# CANcape.net
KiCad netlist of a schematic drawn in EAGLE
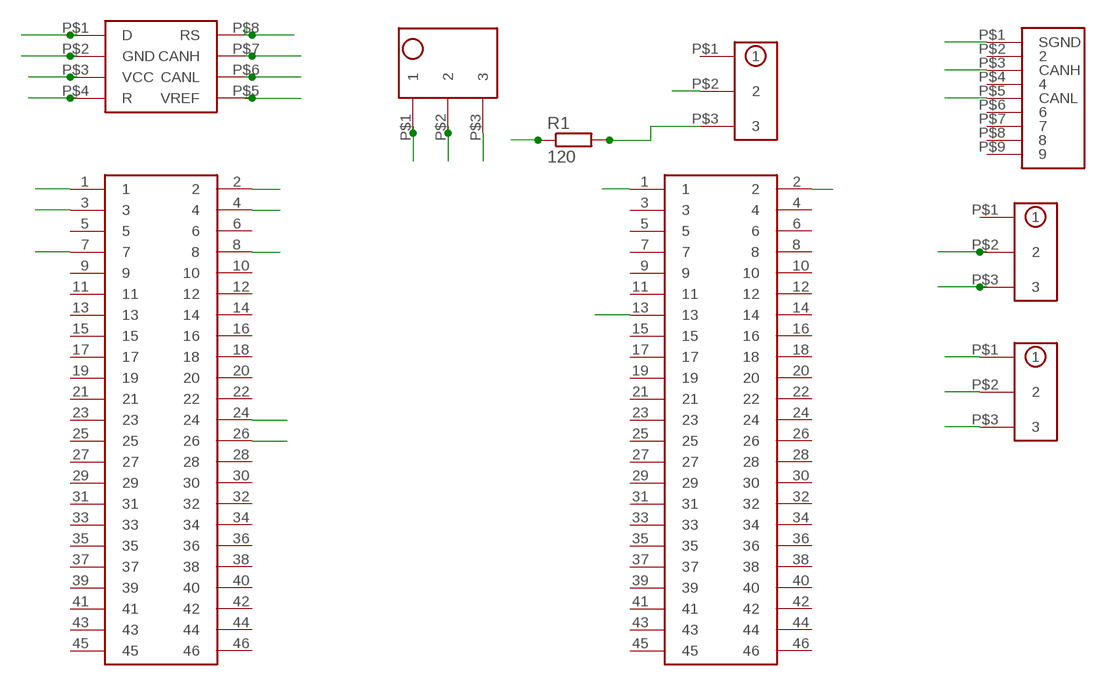
[diagram p0: schematic, sheet 1]

(export (version "E")
  (design (tool "Eeschema 10.0.6"))
  (components
    (comp (ref "R1")
      (value "120")
      (footprint "eagle-import:0207_15")
      (libsource (lib "eagle-import") (part "R-EU_0207/15"))
    )
    (comp (ref "U$1")
      (value "2X23_STACKABLE_HEADERS")
      (footprint "eagle-import:2X23_STACKABLE-HEADERS")
      (libsource (lib "eagle-import") (part "2X23_STACKABLE_HEADERS"))
    )
    (comp (ref "U$2")
      (value "2X23_STACKABLE_HEADERS")
      (footprint "eagle-import:2X23_STACKABLE-HEADERS")
      (libsource (lib "eagle-import") (part "2X23_STACKABLE_HEADERS"))
    )
    (comp (ref "U$3")
      (value "TB-5.0-PT-3P")
      (footprint "eagle-import:TB-5.0-PT-3P")
      (libsource (lib "eagle-import") (part "TB-5.0-PT-3P"))
    )
    (comp (ref "U$4")
      (value "1X3_HEADER")
      (footprint "eagle-import:1X3_HEADER")
      (libsource (lib "eagle-import") (part "1X3_HEADER"))
    )
    (comp (ref "U$5")
      (value "SOIC_BREAKOUT")
      (footprint "eagle-import:SOIC_BREAKOUT")
      (libsource (lib "eagle-import") (part "SOIC_BREAKOUT"))
    )
    (comp (ref "U$6")
      (value "DB9_BREAKOUT")
      (footprint "eagle-import:DB9_BREAKOUT")
      (libsource (lib "eagle-import") (part "DB9_BREAKOUT"))
    )
    (comp (ref "U$7")
      (value "1X3_HEADER")
      (footprint "eagle-import:1X3_HEADER")
      (libsource (lib "eagle-import") (part "1X3_HEADER"))
    )
    (comp (ref "U$8")
      (value "1X3_HEADER")
      (footprint "eagle-import:1X3_HEADER")
      (libsource (lib "eagle-import") (part "1X3_HEADER"))
    )
  )
  (nets
    (net (code "1") (name "/3.3V") (class "Default")
      (node (ref "U$1") (pin "3") (pinfunction "3_3") (pintype "bidirectional"))
      (node (ref "U$1") (pin "4") (pinfunction "4_4") (pintype "bidirectional"))
      (node (ref "U$5") (pin "P$5") (pinfunction "VREF_P$5") (pintype "bidirectional"))
      (node (ref "U$8") (pin "P$1") (pinfunction "1_P$1") (pintype "bidirectional"))
    )
    (net (code "2") (name "/5V") (class "Default")
      (node (ref "U$1") (pin "7") (pinfunction "7_7") (pintype "bidirectional"))
      (node (ref "U$1") (pin "8") (pinfunction "8_8") (pintype "bidirectional"))
      (node (ref "U$8") (pin "P$3") (pinfunction "3_P$3") (pintype "bidirectional"))
    )
    (net (code "3") (name "/CANH") (class "Default")
      (node (ref "U$3") (pin "P$1") (pinfunction "1_P$1") (pintype "bidirectional"))
      (node (ref "U$4") (pin "P$2") (pinfunction "2_P$2") (pintype "bidirectional"))
      (node (ref "U$5") (pin "P$7") (pinfunction "CANH_P$7") (pintype "bidirectional"))
      (node (ref "U$6") (pin "P$3") (pinfunction "CANH_P$3") (pintype "bidirectional"))
    )
    (net (code "4") (name "/CANL") (class "Default")
      (node (ref "R1") (pin "1") (pinfunction "1_1") (pintype "passive"))
      (node (ref "U$3") (pin "P$2") (pinfunction "2_P$2") (pintype "bidirectional"))
      (node (ref "U$5") (pin "P$6") (pinfunction "CANL_P$6") (pintype "bidirectional"))
      (node (ref "U$6") (pin "P$5") (pinfunction "CANL_P$5") (pintype "bidirectional"))
    )
    (net (code "5") (name "/DCAN1_RX") (class "Default")
      (node (ref "U$1") (pin "24") (pinfunction "24_24") (pintype "bidirectional"))
      (node (ref "U$5") (pin "P$4") (pinfunction "R_P$4") (pintype "bidirectional"))
    )
    (net (code "6") (name "/DCAN1_TX") (class "Default")
      (node (ref "U$1") (pin "26") (pinfunction "26_26") (pintype "bidirectional"))
      (node (ref "U$5") (pin "P$1") (pinfunction "D_P$1") (pintype "bidirectional"))
    )
    (net (code "7") (name "/GND") (class "Default")
      (node (ref "U$1") (pin "1") (pinfunction "1_1") (pintype "bidirectional"))
      (node (ref "U$1") (pin "2") (pinfunction "2_2") (pintype "bidirectional"))
      (node (ref "U$2") (pin "1") (pinfunction "1_1") (pintype "bidirectional"))
      (node (ref "U$2") (pin "2") (pinfunction "2_2") (pintype "bidirectional"))
      (node (ref "U$5") (pin "P$2") (pinfunction "GND_P$2") (pintype "bidirectional"))
      (node (ref "U$7") (pin "P$3") (pinfunction "3_P$3") (pintype "bidirectional"))
    )
    (net (code "8") (name "/SGND") (class "Default")
      (node (ref "U$3") (pin "P$3") (pinfunction "3_P$3") (pintype "bidirectional"))
      (node (ref "U$6") (pin "P$1") (pinfunction "SGND_P$1") (pintype "bidirectional"))
      (node (ref "U$7") (pin "P$2") (pinfunction "2_P$2") (pintype "bidirectional"))
    )
    (net (code "9") (name "/STANDBY") (class "Default")
      (node (ref "U$2") (pin "13") (pinfunction "13_13") (pintype "bidirectional"))
      (node (ref "U$5") (pin "P$8") (pinfunction "RS_P$8") (pintype "bidirectional"))
    )
    (net (code "10") (name "/TRAN_PWR") (class "Default")
      (node (ref "U$5") (pin "P$3") (pinfunction "VCC_P$3") (pintype "bidirectional"))
      (node (ref "U$8") (pin "P$2") (pinfunction "2_P$2") (pintype "bidirectional"))
    )
    (net (code "11") (name "Net-(U$4-3)") (class "Default")
      (node (ref "R1") (pin "2") (pinfunction "2_2") (pintype "passive"))
      (node (ref "U$4") (pin "P$3") (pinfunction "3_P$3") (pintype "bidirectional"))
    )
    (net (code "12") (name "unconnected-(U$1-Pad5)") (class "Default")
      (node (ref "U$1") (pin "5") (pinfunction "5_5") (pintype "bidirectional"))
    )
    (net (code "13") (name "unconnected-(U$1-Pad6)") (class "Default")
      (node (ref "U$1") (pin "6") (pinfunction "6_6") (pintype "bidirectional"))
    )
    (net (code "14") (name "unconnected-(U$1-Pad9)") (class "Default")
      (node (ref "U$1") (pin "9") (pinfunction "9_9") (pintype "bidirectional"))
    )
    (net (code "15") (name "unconnected-(U$1-Pad10)") (class "Default")
      (node (ref "U$1") (pin "10") (pinfunction "10_10") (pintype "bidirectional"))
    )
    (net (code "16") (name "unconnected-(U$1-Pad11)") (class "Default")
      (node (ref "U$1") (pin "11") (pinfunction "11_11") (pintype "bidirectional"))
    )
    (net (code "17") (name "unconnected-(U$1-Pad12)") (class "Default")
      (node (ref "U$1") (pin "12") (pinfunction "12_12") (pintype "bidirectional"))
    )
    (net (code "18") (name "unconnected-(U$1-Pad13)") (class "Default")
      (node (ref "U$1") (pin "13") (pinfunction "13_13") (pintype "bidirectional"))
    )
    (net (code "19") (name "unconnected-(U$1-Pad14)") (class "Default")
      (node (ref "U$1") (pin "14") (pinfunction "14_14") (pintype "bidirectional"))
    )
    (net (code "20") (name "unconnected-(U$1-Pad15)") (class "Default")
      (node (ref "U$1") (pin "15") (pinfunction "15_15") (pintype "bidirectional"))
    )
    (net (code "21") (name "unconnected-(U$1-Pad16)") (class "Default")
      (node (ref "U$1") (pin "16") (pinfunction "16_16") (pintype "bidirectional"))
    )
    (net (code "22") (name "unconnected-(U$1-Pad17)") (class "Default")
      (node (ref "U$1") (pin "17") (pinfunction "17_17") (pintype "bidirectional"))
    )
    (net (code "23") (name "unconnected-(U$1-Pad18)") (class "Default")
      (node (ref "U$1") (pin "18") (pinfunction "18_18") (pintype "bidirectional"))
    )
    (net (code "24") (name "unconnected-(U$1-Pad19)") (class "Default")
      (node (ref "U$1") (pin "19") (pinfunction "19_19") (pintype "bidirectional"))
    )
    (net (code "25") (name "unconnected-(U$1-Pad20)") (class "Default")
      (node (ref "U$1") (pin "20") (pinfunction "20_20") (pintype "bidirectional"))
    )
    (net (code "26") (name "unconnected-(U$1-Pad21)") (class "Default")
      (node (ref "U$1") (pin "21") (pinfunction "21_21") (pintype "bidirectional"))
    )
    (net (code "27") (name "unconnected-(U$1-Pad22)") (class "Default")
      (node (ref "U$1") (pin "22") (pinfunction "22_22") (pintype "bidirectional"))
    )
    (net (code "28") (name "unconnected-(U$1-Pad23)") (class "Default")
      (node (ref "U$1") (pin "23") (pinfunction "23_23") (pintype "bidirectional"))
    )
    (net (code "29") (name "unconnected-(U$1-Pad25)") (class "Default")
      (node (ref "U$1") (pin "25") (pinfunction "25_25") (pintype "bidirectional"))
    )
    (net (code "30") (name "unconnected-(U$1-Pad27)") (class "Default")
      (node (ref "U$1") (pin "27") (pinfunction "27_27") (pintype "bidirectional"))
    )
    (net (code "31") (name "unconnected-(U$1-Pad28)") (class "Default")
      (node (ref "U$1") (pin "28") (pinfunction "28_28") (pintype "bidirectional"))
    )
    (net (code "32") (name "unconnected-(U$1-Pad29)") (class "Default")
      (node (ref "U$1") (pin "29") (pinfunction "29_29") (pintype "bidirectional"))
    )
    (net (code "33") (name "unconnected-(U$1-Pad30)") (class "Default")
      (node (ref "U$1") (pin "30") (pinfunction "30_30") (pintype "bidirectional"))
    )
    (net (code "34") (name "unconnected-(U$1-Pad31)") (class "Default")
      (node (ref "U$1") (pin "31") (pinfunction "31_31") (pintype "bidirectional"))
    )
    (net (code "35") (name "unconnected-(U$1-Pad32)") (class "Default")
      (node (ref "U$1") (pin "32") (pinfunction "32_32") (pintype "bidirectional"))
    )
    (net (code "36") (name "unconnected-(U$1-Pad33)") (class "Default")
      (node (ref "U$1") (pin "33") (pinfunction "33_33") (pintype "bidirectional"))
    )
    (net (code "37") (name "unconnected-(U$1-Pad34)") (class "Default")
      (node (ref "U$1") (pin "34") (pinfunction "34_34") (pintype "bidirectional"))
    )
    (net (code "38") (name "unconnected-(U$1-Pad35)") (class "Default")
      (node (ref "U$1") (pin "35") (pinfunction "35_35") (pintype "bidirectional"))
    )
    (net (code "39") (name "unconnected-(U$1-Pad36)") (class "Default")
      (node (ref "U$1") (pin "36") (pinfunction "36_36") (pintype "bidirectional"))
    )
    (net (code "40") (name "unconnected-(U$1-Pad37)") (class "Default")
      (node (ref "U$1") (pin "37") (pinfunction "37_37") (pintype "bidirectional"))
    )
    (net (code "41") (name "unconnected-(U$1-Pad38)") (class "Default")
      (node (ref "U$1") (pin "38") (pinfunction "38_38") (pintype "bidirectional"))
    )
    (net (code "42") (name "unconnected-(U$1-Pad39)") (class "Default")
      (node (ref "U$1") (pin "39") (pinfunction "39_39") (pintype "bidirectional"))
    )
    (net (code "43") (name "unconnected-(U$1-Pad40)") (class "Default")
      (node (ref "U$1") (pin "40") (pinfunction "40_40") (pintype "bidirectional"))
    )
    (net (code "44") (name "unconnected-(U$1-Pad41)") (class "Default")
      (node (ref "U$1") (pin "41") (pinfunction "41_41") (pintype "bidirectional"))
    )
    (net (code "45") (name "unconnected-(U$1-Pad42)") (class "Default")
      (node (ref "U$1") (pin "42") (pinfunction "42_42") (pintype "bidirectional"))
    )
    (net (code "46") (name "unconnected-(U$1-Pad43)") (class "Default")
      (node (ref "U$1") (pin "43") (pinfunction "43_43") (pintype "bidirectional"))
    )
    (net (code "47") (name "unconnected-(U$1-Pad44)") (class "Default")
      (node (ref "U$1") (pin "44") (pinfunction "44_44") (pintype "bidirectional"))
    )
    (net (code "48") (name "unconnected-(U$1-Pad45)") (class "Default")
      (node (ref "U$1") (pin "45") (pinfunction "45_45") (pintype "bidirectional"))
    )
    (net (code "49") (name "unconnected-(U$1-Pad46)") (class "Default")
      (node (ref "U$1") (pin "46") (pinfunction "46_46") (pintype "bidirectional"))
    )
    (net (code "50") (name "unconnected-(U$2-Pad3)") (class "Default")
      (node (ref "U$2") (pin "3") (pinfunction "3_3") (pintype "bidirectional"))
    )
    (net (code "51") (name "unconnected-(U$2-Pad4)") (class "Default")
      (node (ref "U$2") (pin "4") (pinfunction "4_4") (pintype "bidirectional"))
    )
    (net (code "52") (name "unconnected-(U$2-Pad5)") (class "Default")
      (node (ref "U$2") (pin "5") (pinfunction "5_5") (pintype "bidirectional"))
    )
    (net (code "53") (name "unconnected-(U$2-Pad6)") (class "Default")
      (node (ref "U$2") (pin "6") (pinfunction "6_6") (pintype "bidirectional"))
    )
    (net (code "54") (name "unconnected-(U$2-Pad7)") (class "Default")
      (node (ref "U$2") (pin "7") (pinfunction "7_7") (pintype "bidirectional"))
    )
    (net (code "55") (name "unconnected-(U$2-Pad8)") (class "Default")
      (node (ref "U$2") (pin "8") (pinfunction "8_8") (pintype "bidirectional"))
    )
    (net (code "56") (name "unconnected-(U$2-Pad9)") (class "Default")
      (node (ref "U$2") (pin "9") (pinfunction "9_9") (pintype "bidirectional"))
    )
    (net (code "57") (name "unconnected-(U$2-Pad10)") (class "Default")
      (node (ref "U$2") (pin "10") (pinfunction "10_10") (pintype "bidirectional"))
    )
    (net (code "58") (name "unconnected-(U$2-Pad11)") (class "Default")
      (node (ref "U$2") (pin "11") (pinfunction "11_11") (pintype "bidirectional"))
    )
    (net (code "59") (name "unconnected-(U$2-Pad12)") (class "Default")
      (node (ref "U$2") (pin "12") (pinfunction "12_12") (pintype "bidirectional"))
    )
    (net (code "60") (name "unconnected-(U$2-Pad14)") (class "Default")
      (node (ref "U$2") (pin "14") (pinfunction "14_14") (pintype "bidirectional"))
    )
    (net (code "61") (name "unconnected-(U$2-Pad15)") (class "Default")
      (node (ref "U$2") (pin "15") (pinfunction "15_15") (pintype "bidirectional"))
    )
    (net (code "62") (name "unconnected-(U$2-Pad16)") (class "Default")
      (node (ref "U$2") (pin "16") (pinfunction "16_16") (pintype "bidirectional"))
    )
    (net (code "63") (name "unconnected-(U$2-Pad17)") (class "Default")
      (node (ref "U$2") (pin "17") (pinfunction "17_17") (pintype "bidirectional"))
    )
    (net (code "64") (name "unconnected-(U$2-Pad18)") (class "Default")
      (node (ref "U$2") (pin "18") (pinfunction "18_18") (pintype "bidirectional"))
    )
    (net (code "65") (name "unconnected-(U$2-Pad19)") (class "Default")
      (node (ref "U$2") (pin "19") (pinfunction "19_19") (pintype "bidirectional"))
    )
    (net (code "66") (name "unconnected-(U$2-Pad20)") (class "Default")
      (node (ref "U$2") (pin "20") (pinfunction "20_20") (pintype "bidirectional"))
    )
    (net (code "67") (name "unconnected-(U$2-Pad21)") (class "Default")
      (node (ref "U$2") (pin "21") (pinfunction "21_21") (pintype "bidirectional"))
    )
    (net (code "68") (name "unconnected-(U$2-Pad22)") (class "Default")
      (node (ref "U$2") (pin "22") (pinfunction "22_22") (pintype "bidirectional"))
    )
    (net (code "69") (name "unconnected-(U$2-Pad23)") (class "Default")
      (node (ref "U$2") (pin "23") (pinfunction "23_23") (pintype "bidirectional"))
    )
    (net (code "70") (name "unconnected-(U$2-Pad24)") (class "Default")
      (node (ref "U$2") (pin "24") (pinfunction "24_24") (pintype "bidirectional"))
    )
    (net (code "71") (name "unconnected-(U$2-Pad25)") (class "Default")
      (node (ref "U$2") (pin "25") (pinfunction "25_25") (pintype "bidirectional"))
    )
    (net (code "72") (name "unconnected-(U$2-Pad26)") (class "Default")
      (node (ref "U$2") (pin "26") (pinfunction "26_26") (pintype "bidirectional"))
    )
    (net (code "73") (name "unconnected-(U$2-Pad27)") (class "Default")
      (node (ref "U$2") (pin "27") (pinfunction "27_27") (pintype "bidirectional"))
    )
    (net (code "74") (name "unconnected-(U$2-Pad28)") (class "Default")
      (node (ref "U$2") (pin "28") (pinfunction "28_28") (pintype "bidirectional"))
    )
    (net (code "75") (name "unconnected-(U$2-Pad29)") (class "Default")
      (node (ref "U$2") (pin "29") (pinfunction "29_29") (pintype "bidirectional"))
    )
    (net (code "76") (name "unconnected-(U$2-Pad30)") (class "Default")
      (node (ref "U$2") (pin "30") (pinfunction "30_30") (pintype "bidirectional"))
    )
    (net (code "77") (name "unconnected-(U$2-Pad31)") (class "Default")
      (node (ref "U$2") (pin "31") (pinfunction "31_31") (pintype "bidirectional"))
    )
    (net (code "78") (name "unconnected-(U$2-Pad32)") (class "Default")
      (node (ref "U$2") (pin "32") (pinfunction "32_32") (pintype "bidirectional"))
    )
    (net (code "79") (name "unconnected-(U$2-Pad33)") (class "Default")
      (node (ref "U$2") (pin "33") (pinfunction "33_33") (pintype "bidirectional"))
    )
    (net (code "80") (name "unconnected-(U$2-Pad34)") (class "Default")
      (node (ref "U$2") (pin "34") (pinfunction "34_34") (pintype "bidirectional"))
    )
    (net (code "81") (name "unconnected-(U$2-Pad35)") (class "Default")
      (node (ref "U$2") (pin "35") (pinfunction "35_35") (pintype "bidirectional"))
    )
    (net (code "82") (name "unconnected-(U$2-Pad36)") (class "Default")
      (node (ref "U$2") (pin "36") (pinfunction "36_36") (pintype "bidirectional"))
    )
    (net (code "83") (name "unconnected-(U$2-Pad37)") (class "Default")
      (node (ref "U$2") (pin "37") (pinfunction "37_37") (pintype "bidirectional"))
    )
    (net (code "84") (name "unconnected-(U$2-Pad38)") (class "Default")
      (node (ref "U$2") (pin "38") (pinfunction "38_38") (pintype "bidirectional"))
    )
    (net (code "85") (name "unconnected-(U$2-Pad39)") (class "Default")
      (node (ref "U$2") (pin "39") (pinfunction "39_39") (pintype "bidirectional"))
    )
    (net (code "86") (name "unconnected-(U$2-Pad40)") (class "Default")
      (node (ref "U$2") (pin "40") (pinfunction "40_40") (pintype "bidirectional"))
    )
    (net (code "87") (name "unconnected-(U$2-Pad41)") (class "Default")
      (node (ref "U$2") (pin "41") (pinfunction "41_41") (pintype "bidirectional"))
    )
    (net (code "88") (name "unconnected-(U$2-Pad42)") (class "Default")
      (node (ref "U$2") (pin "42") (pinfunction "42_42") (pintype "bidirectional"))
    )
    (net (code "89") (name "unconnected-(U$2-Pad43)") (class "Default")
      (node (ref "U$2") (pin "43") (pinfunction "43_43") (pintype "bidirectional"))
    )
    (net (code "90") (name "unconnected-(U$2-Pad44)") (class "Default")
      (node (ref "U$2") (pin "44") (pinfunction "44_44") (pintype "bidirectional"))
    )
    (net (code "91") (name "unconnected-(U$2-Pad45)") (class "Default")
      (node (ref "U$2") (pin "45") (pinfunction "45_45") (pintype "bidirectional"))
    )
    (net (code "92") (name "unconnected-(U$2-Pad46)") (class "Default")
      (node (ref "U$2") (pin "46") (pinfunction "46_46") (pintype "bidirectional"))
    )
    (net (code "93") (name "unconnected-(U$4-1-PadP$1)") (class "Default")
      (node (ref "U$4") (pin "P$1") (pinfunction "1_P$1") (pintype "bidirectional"))
    )
    (net (code "94") (name "unconnected-(U$6-2-PadP$2)") (class "Default")
      (node (ref "U$6") (pin "P$2") (pinfunction "2_P$2") (pintype "bidirectional"))
    )
    (net (code "95") (name "unconnected-(U$6-4-PadP$4)") (class "Default")
      (node (ref "U$6") (pin "P$4") (pinfunction "4_P$4") (pintype "bidirectional"))
    )
    (net (code "96") (name "unconnected-(U$6-6-PadP$6)") (class "Default")
      (node (ref "U$6") (pin "P$6") (pinfunction "6_P$6") (pintype "bidirectional"))
    )
    (net (code "97") (name "unconnected-(U$6-7-PadP$7)") (class "Default")
      (node (ref "U$6") (pin "P$7") (pinfunction "7_P$7") (pintype "bidirectional"))
    )
    (net (code "98") (name "unconnected-(U$6-8-PadP$8)") (class "Default")
      (node (ref "U$6") (pin "P$8") (pinfunction "8_P$8") (pintype "bidirectional"))
    )
    (net (code "99") (name "unconnected-(U$6-9-PadP$9)") (class "Default")
      (node (ref "U$6") (pin "P$9") (pinfunction "9_P$9") (pintype "bidirectional"))
    )
    (net (code "100") (name "unconnected-(U$7-1-PadP$1)") (class "Default")
      (node (ref "U$7") (pin "P$1") (pinfunction "1_P$1") (pintype "bidirectional"))
    )
  )
)
